# lpc1114_basic.net
KiCad netlist of a schematic drawn in EAGLE
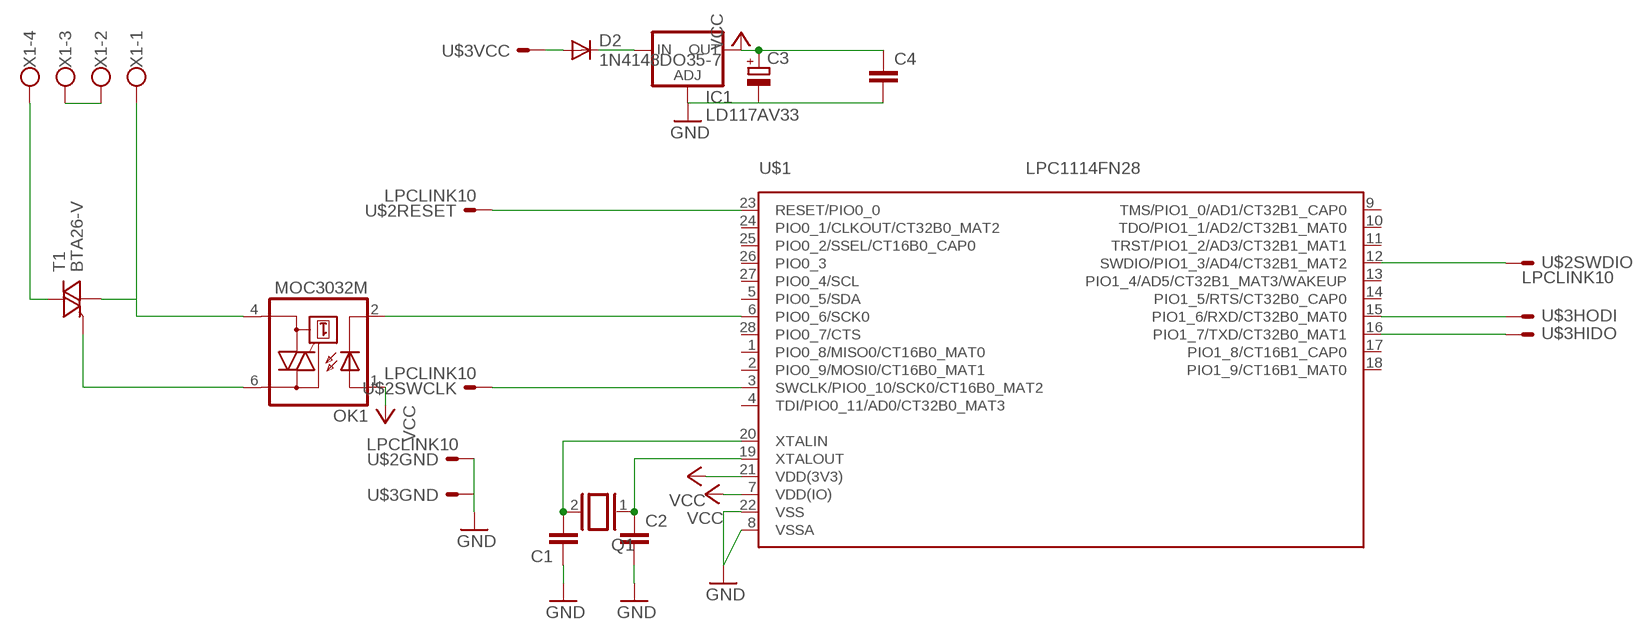
[diagram p0: schematic, sheet 1]

(export (version "E")
  (design (tool "Eeschema 10.0.6"))
  (components
    (comp (ref "C1")
      (value "C-EU025-024X044")
      (footprint "eagle-import:C025-024X044")
      (libsource (lib "eagle-import") (part "C-EU025-024X044"))
    )
    (comp (ref "C2")
      (value "C-EU025-024X044")
      (footprint "eagle-import:C025-024X044")
      (libsource (lib "eagle-import") (part "C-EU025-024X044"))
    )
    (comp (ref "C3")
      (value "CPOL-EUTT2D6")
      (footprint "eagle-import:TT2D6")
      (libsource (lib "eagle-import") (part "CPOL-EUTT2D6"))
    )
    (comp (ref "C4")
      (value "C-EU050-024X044")
      (footprint "eagle-import:C050-024X044")
      (libsource (lib "eagle-import") (part "C-EU050-024X044"))
    )
    (comp (ref "D2")
      (value "1N4148DO35-7")
      (footprint "eagle-import:DO35-7")
      (libsource (lib "eagle-import") (part "1N4148DO35-7"))
    )
    (comp (ref "IC1")
      (value "LD117AV33")
      (footprint "eagle-import:TO220L1")
      (libsource (lib "eagle-import") (part "LD117A?V33"))
    )
    (comp (ref "OK1")
      (value "MOC3032M")
      (footprint "eagle-import:DIL06")
      (fields (field (name "MF") "FAIRCHILD SEMICONDUCTOR") (field (name "MPN") "MOC3032-M"))
      (libsource (lib "eagle-import") (part "MOC3032M"))
    )
    (comp (ref "Q1")
      (value "XTAL/S")
      (footprint "eagle-import:QS")
      (libsource (lib "eagle-import") (part "XTAL/S"))
    )
    (comp (ref "T1")
      (value "BTA26-V")
      (footprint "eagle-import:TOP3S-1")
      (libsource (lib "eagle-import") (part "BTA26-V"))
    )
    (comp (ref "U$1")
      (value "LPC1114FN28")
      (footprint "eagle-import:DIP28")
      (libsource (lib "eagle-import") (part "LPC1114FN28"))
    )
    (comp (ref "U$2")
      (value "LPCLINK10")
      (footprint "eagle-import:ML10")
      (libsource (lib "eagle-import") (part "LPCLINK10"))
    )
    (comp (ref "U$3")
      (value "UARTUSB")
      (footprint "eagle-import:PN61729")
      (libsource (lib "eagle-import") (part "UARTUSB"))
    )
    (comp (ref "X1")
      (value "W237-4")
      (footprint "eagle-import:W237-4")
      (libsource (lib "eagle-import") (part "W237-4"))
    )
  )
  (nets
    (net (code "1") (name "GND") (class "Default")
      (node (ref "C1") (pin "1") (pinfunction "1_1") (pintype "passive"))
      (node (ref "C2") (pin "2") (pinfunction "2_2") (pintype "passive"))
      (node (ref "C3") (pin "-") (pinfunction "-_-") (pintype "passive"))
      (node (ref "C4") (pin "2") (pinfunction "2_2") (pintype "passive"))
      (node (ref "IC1") (pin "1") (pinfunction "ADJ_1") (pintype "input"))
      (node (ref "U$1") (pin "22") (pinfunction "VSS_22") (pintype "power_in"))
      (node (ref "U$1") (pin "8") (pinfunction "VSSA_8") (pintype "power_in"))
      (node (ref "U$2") (pin "9") (pinfunction "S_9") (pintype "passive"))
      (node (ref "U$3") (pin "4") (pinfunction "S_4") (pintype "passive"))
    )
    (net (code "2") (name "Net-(IC1-IN)") (class "Default")
      (node (ref "D2") (pin "C") (pinfunction "C_C") (pintype "passive"))
      (node (ref "IC1") (pin "3") (pinfunction "IN_3") (pintype "input"))
    )
    (net (code "3") (name "Net-(OK1-A1)") (class "Default")
      (node (ref "OK1") (pin "4") (pinfunction "A1_4") (pintype "passive"))
      (node (ref "T1") (pin "A1") (pinfunction "A1_A1") (pintype "passive"))
      (node (ref "X1") (pin "1") (pinfunction "KL_1") (pintype "passive"))
    )
    (net (code "4") (name "Net-(OK1-A2)") (class "Default")
      (node (ref "OK1") (pin "6") (pinfunction "A2_6") (pintype "passive"))
      (node (ref "T1") (pin "G") (pinfunction "G_G") (pintype "passive"))
    )
    (net (code "5") (name "Net-(OK1-C)") (class "Default")
      (node (ref "OK1") (pin "2") (pinfunction "C_2") (pintype "passive"))
      (node (ref "U$1") (pin "6") (pinfunction "PIO0_6/SCK0_6") (pintype "bidirectional"))
    )
    (net (code "6") (name "Net-(U$1-PIO1_6{slash}RXD{slash}CT32B0_MAT0)") (class "Default")
      (node (ref "U$1") (pin "15") (pinfunction "PIO1_6/RXD/CT32B0_MAT0_15") (pintype "bidirectional"))
      (node (ref "U$3") (pin "3") (pinfunction "S_3") (pintype "passive"))
    )
    (net (code "7") (name "Net-(U$1-PIO1_7{slash}TXD{slash}CT32B0_MAT1)") (class "Default")
      (node (ref "U$1") (pin "16") (pinfunction "PIO1_7/TXD/CT32B0_MAT1_16") (pintype "bidirectional"))
      (node (ref "U$3") (pin "2") (pinfunction "S_2") (pintype "passive"))
    )
    (net (code "8") (name "Net-(U$1-RESET{slash}PIO0_0)") (class "Default")
      (node (ref "U$1") (pin "23") (pinfunction "RESET/PIO0_0_23") (pintype "bidirectional"))
      (node (ref "U$2") (pin "10") (pinfunction "S_10") (pintype "passive"))
    )
    (net (code "9") (name "Net-(U$1-SWCLK{slash}PIO0_10{slash}SCK0{slash}CT16B0_MAT2)") (class "Default")
      (node (ref "U$1") (pin "3") (pinfunction "SWCLK/PIO0_10/SCK0/CT16B0_MAT2_3") (pintype "bidirectional"))
      (node (ref "U$2") (pin "4") (pinfunction "S_4") (pintype "passive"))
    )
    (net (code "10") (name "Net-(U$1-SWDIO{slash}PIO1_3{slash}AD4{slash}CT32B1_MAT2)") (class "Default")
      (node (ref "U$1") (pin "12") (pinfunction "SWDIO/PIO1_3/AD4/CT32B1_MAT2_12") (pintype "bidirectional"))
      (node (ref "U$2") (pin "2") (pinfunction "S_2") (pintype "passive"))
    )
    (net (code "11") (name "Net-(U$1-XTALIN)") (class "Default")
      (node (ref "C1") (pin "2") (pinfunction "2_2") (pintype "passive"))
      (node (ref "Q1") (pin "2") (pinfunction "2_2") (pintype "passive"))
      (node (ref "U$1") (pin "20") (pinfunction "XTALIN_20") (pintype "input"))
    )
    (net (code "12") (name "Net-(U$1-XTALOUT)") (class "Default")
      (node (ref "C2") (pin "1") (pinfunction "1_1") (pintype "passive"))
      (node (ref "Q1") (pin "1") (pinfunction "1_1") (pintype "passive"))
      (node (ref "U$1") (pin "19") (pinfunction "XTALOUT_19") (pintype "output"))
    )
    (net (code "13") (name "Net-(U$3D-S)") (class "Default")
      (node (ref "D2") (pin "A") (pinfunction "A_A") (pintype "passive"))
      (node (ref "U$3") (pin "1") (pinfunction "S_1") (pintype "passive"))
    )
    (net (code "14") (name "Net-(X1B-KL)") (class "Default")
      (node (ref "X1") (pin "2") (pinfunction "KL_2") (pintype "passive"))
      (node (ref "X1") (pin "3") (pinfunction "KL_3") (pintype "passive"))
    )
    (net (code "15") (name "Net-(X1D-KL)") (class "Default")
      (node (ref "T1") (pin "A2") (pinfunction "A2_A2") (pintype "passive"))
      (node (ref "X1") (pin "4") (pinfunction "KL_4") (pintype "passive"))
    )
    (net (code "16") (name "VCC") (class "Default")
      (node (ref "C3") (pin "+") (pinfunction "+_+") (pintype "passive"))
      (node (ref "C4") (pin "1") (pinfunction "1_1") (pintype "passive"))
      (node (ref "IC1") (pin "2") (pinfunction "OUT_2") (pintype "passive"))
      (node (ref "OK1") (pin "1") (pinfunction "A_1") (pintype "passive"))
      (node (ref "U$1") (pin "21") (pinfunction "VDD(3V3)_21") (pintype "power_in"))
      (node (ref "U$1") (pin "7") (pinfunction "VDD(IO)_7") (pintype "power_in"))
    )
    (net (code "17") (name "unconnected-(U$1-PIO0_1{slash}CLKOUT{slash}CT32B0_MAT2-Pad24)") (class "Default")
      (node (ref "U$1") (pin "24") (pinfunction "PIO0_1/CLKOUT/CT32B0_MAT2_24") (pintype "bidirectional"))
    )
    (net (code "18") (name "unconnected-(U$1-PIO0_2{slash}SSEL{slash}CT16B0_CAP0-Pad25)") (class "Default")
      (node (ref "U$1") (pin "25") (pinfunction "PIO0_2/SSEL/CT16B0_CAP0_25") (pintype "bidirectional"))
    )
    (net (code "19") (name "unconnected-(U$1-PIO0_3-Pad26)") (class "Default")
      (node (ref "U$1") (pin "26") (pinfunction "PIO0_3_26") (pintype "bidirectional"))
    )
    (net (code "20") (name "unconnected-(U$1-PIO0_4{slash}SCL-Pad27)") (class "Default")
      (node (ref "U$1") (pin "27") (pinfunction "PIO0_4/SCL_27") (pintype "bidirectional"))
    )
    (net (code "21") (name "unconnected-(U$1-PIO0_5{slash}SDA-Pad5)") (class "Default")
      (node (ref "U$1") (pin "5") (pinfunction "PIO0_5/SDA_5") (pintype "bidirectional"))
    )
    (net (code "22") (name "unconnected-(U$1-PIO0_7{slash}CTS-Pad28)") (class "Default")
      (node (ref "U$1") (pin "28") (pinfunction "PIO0_7/CTS_28") (pintype "bidirectional"))
    )
    (net (code "23") (name "unconnected-(U$1-PIO0_8{slash}MISO0{slash}CT16B0_MAT0-Pad1)") (class "Default")
      (node (ref "U$1") (pin "1") (pinfunction "PIO0_8/MISO0/CT16B0_MAT0_1") (pintype "bidirectional"))
    )
    (net (code "24") (name "unconnected-(U$1-PIO0_9{slash}MOSI0{slash}CT16B0_MAT1-Pad2)") (class "Default")
      (node (ref "U$1") (pin "2") (pinfunction "PIO0_9/MOSI0/CT16B0_MAT1_2") (pintype "bidirectional"))
    )
    (net (code "25") (name "unconnected-(U$1-PIO1_4{slash}AD5{slash}CT32B1_MAT3{slash}WAKEUP-Pad13)") (class "Default")
      (node (ref "U$1") (pin "13") (pinfunction "PIO1_4/AD5/CT32B1_MAT3/WAKEUP_13") (pintype "bidirectional"))
    )
    (net (code "26") (name "unconnected-(U$1-PIO1_5{slash}RTS{slash}CT32B0_CAP0-Pad14)") (class "Default")
      (node (ref "U$1") (pin "14") (pinfunction "PIO1_5/RTS/CT32B0_CAP0_14") (pintype "bidirectional"))
    )
    (net (code "27") (name "unconnected-(U$1-PIO1_8{slash}CT16B1_CAP0-Pad17)") (class "Default")
      (node (ref "U$1") (pin "17") (pinfunction "PIO1_8/CT16B1_CAP0_17") (pintype "bidirectional"))
    )
    (net (code "28") (name "unconnected-(U$1-PIO1_9{slash}CT16B1_MAT0-Pad18)") (class "Default")
      (node (ref "U$1") (pin "18") (pinfunction "PIO1_9/CT16B1_MAT0_18") (pintype "bidirectional"))
    )
    (net (code "29") (name "unconnected-(U$1-TDI{slash}PIO0_11{slash}AD0{slash}CT32B0_MAT3-Pad4)") (class "Default")
      (node (ref "U$1") (pin "4") (pinfunction "TDI/PIO0_11/AD0/CT32B0_MAT3_4") (pintype "bidirectional"))
    )
    (net (code "30") (name "unconnected-(U$1-TDO{slash}PIO1_1{slash}AD2{slash}CT32B1_MAT0-Pad10)") (class "Default")
      (node (ref "U$1") (pin "10") (pinfunction "TDO/PIO1_1/AD2/CT32B1_MAT0_10") (pintype "bidirectional"))
    )
    (net (code "31") (name "unconnected-(U$1-TMS{slash}PIO1_0{slash}AD1{slash}CT32B1_CAP0-Pad9)") (class "Default")
      (node (ref "U$1") (pin "9") (pinfunction "TMS/PIO1_0/AD1/CT32B1_CAP0_9") (pintype "bidirectional"))
    )
    (net (code "32") (name "unconnected-(U$1-TRST{slash}PIO1_2{slash}AD3{slash}CT32B1_MAT1-Pad11)") (class "Default")
      (node (ref "U$1") (pin "11") (pinfunction "TRST/PIO1_2/AD3/CT32B1_MAT1_11") (pintype "bidirectional"))
    )
  )
)
